# V1_PWM-to-analog_sch.net
KiCad netlist of a schematic drawn in Altium Designer
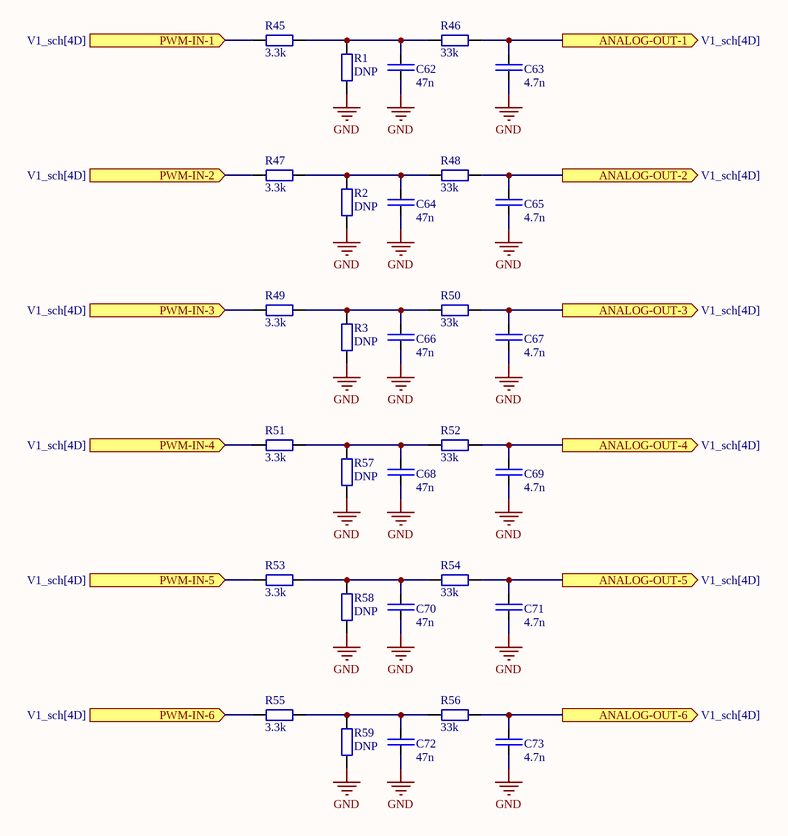
[diagram p0: V1_PWM-to-analog_sch.SchDoc]

(export (version "E")
  (design (tool "Eeschema 10.0.6"))
  (components
    (comp (ref "C62")
      (value "47n")
      (footprint "Passives:FPR_0603_C_R0")
      (description "Capacitor - generic SMD")
      (fields (field (name "Comment") "PN_C0603_TBD"))
      (libsource (lib "Passives") (part "C"))
    )
    (comp (ref "C63")
      (value "4.7n")
      (footprint "Passives:FPR_0603_C_R0")
      (description "Capacitor - generic SMD")
      (fields (field (name "Comment") "PN_C0603_TBD"))
      (libsource (lib "Passives") (part "C"))
    )
    (comp (ref "C64")
      (value "47n")
      (footprint "Passives:FPR_0603_C_R0")
      (description "Capacitor - generic SMD")
      (fields (field (name "Comment") "PN_C0603_TBD"))
      (libsource (lib "Passives") (part "C"))
    )
    (comp (ref "C65")
      (value "4.7n")
      (footprint "Passives:FPR_0603_C_R0")
      (description "Capacitor - generic SMD")
      (fields (field (name "Comment") "PN_C0603_TBD"))
      (libsource (lib "Passives") (part "C"))
    )
    (comp (ref "C66")
      (value "47n")
      (footprint "Passives:FPR_0603_C_R0")
      (description "Capacitor - generic SMD")
      (fields (field (name "Comment") "PN_C0603_TBD"))
      (libsource (lib "Passives") (part "C"))
    )
    (comp (ref "C67")
      (value "4.7n")
      (footprint "Passives:FPR_0603_C_R0")
      (description "Capacitor - generic SMD")
      (fields (field (name "Comment") "PN_C0603_TBD"))
      (libsource (lib "Passives") (part "C"))
    )
    (comp (ref "C68")
      (value "47n")
      (footprint "Passives:FPR_0603_C_R0")
      (description "Capacitor - generic SMD")
      (fields (field (name "Comment") "PN_C0603_TBD"))
      (libsource (lib "Passives") (part "C"))
    )
    (comp (ref "C69")
      (value "4.7n")
      (footprint "Passives:FPR_0603_C_R0")
      (description "Capacitor - generic SMD")
      (fields (field (name "Comment") "PN_C0603_TBD"))
      (libsource (lib "Passives") (part "C"))
    )
    (comp (ref "C70")
      (value "47n")
      (footprint "Passives:FPR_0603_C_R0")
      (description "Capacitor - generic SMD")
      (fields (field (name "Comment") "PN_C0603_TBD"))
      (libsource (lib "Passives") (part "C"))
    )
    (comp (ref "C71")
      (value "4.7n")
      (footprint "Passives:FPR_0603_C_R0")
      (description "Capacitor - generic SMD")
      (fields (field (name "Comment") "PN_C0603_TBD"))
      (libsource (lib "Passives") (part "C"))
    )
    (comp (ref "C72")
      (value "47n")
      (footprint "Passives:FPR_0603_C_R0")
      (description "Capacitor - generic SMD")
      (fields (field (name "Comment") "PN_C0603_TBD"))
      (libsource (lib "Passives") (part "C"))
    )
    (comp (ref "C73")
      (value "4.7n")
      (footprint "Passives:FPR_0603_C_R0")
      (description "Capacitor - generic SMD")
      (fields (field (name "Comment") "PN_C0603_TBD"))
      (libsource (lib "Passives") (part "C"))
    )
    (comp (ref "R1")
      (value "DNP")
      (footprint "Passives:FPR_0603_R_R0")
      (description "Resistor - generic SMD")
      (fields (field (name "Comment") "PN_R0603_TBD"))
      (libsource (lib "Passives") (part "R"))
    )
    (comp (ref "R2")
      (value "DNP")
      (footprint "Passives:FPR_0603_R_R0")
      (description "Resistor - generic SMD")
      (fields (field (name "Comment") "PN_R0603_TBD"))
      (libsource (lib "Passives") (part "R"))
    )
    (comp (ref "R3")
      (value "DNP")
      (footprint "Passives:FPR_0603_R_R0")
      (description "Resistor - generic SMD")
      (fields (field (name "Comment") "PN_R0603_TBD"))
      (libsource (lib "Passives") (part "R"))
    )
    (comp (ref "R45")
      (value "3.3k")
      (footprint "Passives:FPR_0603_R_R0")
      (description "Resistor - generic SMD")
      (fields (field (name "Comment") "PN_R0603_TBD"))
      (libsource (lib "Passives") (part "R"))
    )
    (comp (ref "R46")
      (value "33k")
      (footprint "Passives:FPR_0603_R_R0")
      (description "Resistor - generic SMD")
      (fields (field (name "Comment") "PN_R0603_TBD"))
      (libsource (lib "Passives") (part "R"))
    )
    (comp (ref "R47")
      (value "3.3k")
      (footprint "Passives:FPR_0603_R_R0")
      (description "Resistor - generic SMD")
      (fields (field (name "Comment") "PN_R0603_TBD"))
      (libsource (lib "Passives") (part "R"))
    )
    (comp (ref "R48")
      (value "33k")
      (footprint "Passives:FPR_0603_R_R0")
      (description "Resistor - generic SMD")
      (fields (field (name "Comment") "PN_R0603_TBD"))
      (libsource (lib "Passives") (part "R"))
    )
    (comp (ref "R49")
      (value "3.3k")
      (footprint "Passives:FPR_0603_R_R0")
      (description "Resistor - generic SMD")
      (fields (field (name "Comment") "PN_R0603_TBD"))
      (libsource (lib "Passives") (part "R"))
    )
    (comp (ref "R50")
      (value "33k")
      (footprint "Passives:FPR_0603_R_R0")
      (description "Resistor - generic SMD")
      (fields (field (name "Comment") "PN_R0603_TBD"))
      (libsource (lib "Passives") (part "R"))
    )
    (comp (ref "R51")
      (value "3.3k")
      (footprint "Passives:FPR_0603_R_R0")
      (description "Resistor - generic SMD")
      (fields (field (name "Comment") "PN_R0603_TBD"))
      (libsource (lib "Passives") (part "R"))
    )
    (comp (ref "R52")
      (value "33k")
      (footprint "Passives:FPR_0603_R_R0")
      (description "Resistor - generic SMD")
      (fields (field (name "Comment") "PN_R0603_TBD"))
      (libsource (lib "Passives") (part "R"))
    )
    (comp (ref "R53")
      (value "3.3k")
      (footprint "Passives:FPR_0603_R_R0")
      (description "Resistor - generic SMD")
      (fields (field (name "Comment") "PN_R0603_TBD"))
      (libsource (lib "Passives") (part "R"))
    )
    (comp (ref "R54")
      (value "33k")
      (footprint "Passives:FPR_0603_R_R0")
      (description "Resistor - generic SMD")
      (fields (field (name "Comment") "PN_R0603_TBD"))
      (libsource (lib "Passives") (part "R"))
    )
    (comp (ref "R55")
      (value "3.3k")
      (footprint "Passives:FPR_0603_R_R0")
      (description "Resistor - generic SMD")
      (fields (field (name "Comment") "PN_R0603_TBD"))
      (libsource (lib "Passives") (part "R"))
    )
    (comp (ref "R56")
      (value "33k")
      (footprint "Passives:FPR_0603_R_R0")
      (description "Resistor - generic SMD")
      (fields (field (name "Comment") "PN_R0603_TBD"))
      (libsource (lib "Passives") (part "R"))
    )
    (comp (ref "R57")
      (value "DNP")
      (footprint "Passives:FPR_0603_R_R0")
      (description "Resistor - generic SMD")
      (fields (field (name "Comment") "PN_R0603_TBD"))
      (libsource (lib "Passives") (part "R"))
    )
    (comp (ref "R58")
      (value "DNP")
      (footprint "Passives:FPR_0603_R_R0")
      (description "Resistor - generic SMD")
      (fields (field (name "Comment") "PN_R0603_TBD"))
      (libsource (lib "Passives") (part "R"))
    )
    (comp (ref "R59")
      (value "DNP")
      (footprint "Passives:FPR_0603_R_R0")
      (description "Resistor - generic SMD")
      (fields (field (name "Comment") "PN_R0603_TBD"))
      (libsource (lib "Passives") (part "R"))
    )
  )
  (nets
    (net (code "1") (name "/ANALOG-OUT-1") (class "Default")
      (node (ref "C63") (pin "2") (pinfunction "2_2") (pintype "passive"))
      (node (ref "R46") (pin "1") (pinfunction "1_1") (pintype "passive"))
    )
    (net (code "2") (name "/ANALOG-OUT-2") (class "Default")
      (node (ref "C65") (pin "2") (pinfunction "2_2") (pintype "passive"))
      (node (ref "R48") (pin "1") (pinfunction "1_1") (pintype "passive"))
    )
    (net (code "3") (name "/ANALOG-OUT-3") (class "Default")
      (node (ref "C67") (pin "2") (pinfunction "2_2") (pintype "passive"))
      (node (ref "R50") (pin "1") (pinfunction "1_1") (pintype "passive"))
    )
    (net (code "4") (name "/ANALOG-OUT-4") (class "Default")
      (node (ref "C69") (pin "2") (pinfunction "2_2") (pintype "passive"))
      (node (ref "R52") (pin "1") (pinfunction "1_1") (pintype "passive"))
    )
    (net (code "5") (name "/ANALOG-OUT-5") (class "Default")
      (node (ref "C71") (pin "2") (pinfunction "2_2") (pintype "passive"))
      (node (ref "R54") (pin "1") (pinfunction "1_1") (pintype "passive"))
    )
    (net (code "6") (name "/ANALOG-OUT-6") (class "Default")
      (node (ref "C73") (pin "2") (pinfunction "2_2") (pintype "passive"))
      (node (ref "R56") (pin "1") (pinfunction "1_1") (pintype "passive"))
    )
    (net (code "7") (name "/PWM-IN-1") (class "Default")
      (node (ref "R45") (pin "2") (pinfunction "2_2") (pintype "passive"))
    )
    (net (code "8") (name "/PWM-IN-2") (class "Default")
      (node (ref "R47") (pin "2") (pinfunction "2_2") (pintype "passive"))
    )
    (net (code "9") (name "/PWM-IN-3") (class "Default")
      (node (ref "R49") (pin "2") (pinfunction "2_2") (pintype "passive"))
    )
    (net (code "10") (name "/PWM-IN-4") (class "Default")
      (node (ref "R51") (pin "2") (pinfunction "2_2") (pintype "passive"))
    )
    (net (code "11") (name "/PWM-IN-5") (class "Default")
      (node (ref "R53") (pin "2") (pinfunction "2_2") (pintype "passive"))
    )
    (net (code "12") (name "/PWM-IN-6") (class "Default")
      (node (ref "R55") (pin "2") (pinfunction "2_2") (pintype "passive"))
    )
    (net (code "13") (name "GND") (class "Default")
      (node (ref "C62") (pin "1") (pinfunction "1_1") (pintype "passive"))
      (node (ref "C63") (pin "1") (pinfunction "1_1") (pintype "passive"))
      (node (ref "C64") (pin "1") (pinfunction "1_1") (pintype "passive"))
      (node (ref "C65") (pin "1") (pinfunction "1_1") (pintype "passive"))
      (node (ref "C66") (pin "1") (pinfunction "1_1") (pintype "passive"))
      (node (ref "C67") (pin "1") (pinfunction "1_1") (pintype "passive"))
      (node (ref "C68") (pin "1") (pinfunction "1_1") (pintype "passive"))
      (node (ref "C69") (pin "1") (pinfunction "1_1") (pintype "passive"))
      (node (ref "C70") (pin "1") (pinfunction "1_1") (pintype "passive"))
      (node (ref "C71") (pin "1") (pinfunction "1_1") (pintype "passive"))
      (node (ref "C72") (pin "1") (pinfunction "1_1") (pintype "passive"))
      (node (ref "C73") (pin "1") (pinfunction "1_1") (pintype "passive"))
      (node (ref "R1") (pin "2") (pinfunction "2_2") (pintype "passive"))
      (node (ref "R2") (pin "2") (pinfunction "2_2") (pintype "passive"))
      (node (ref "R3") (pin "2") (pinfunction "2_2") (pintype "passive"))
      (node (ref "R57") (pin "2") (pinfunction "2_2") (pintype "passive"))
      (node (ref "R58") (pin "2") (pinfunction "2_2") (pintype "passive"))
      (node (ref "R59") (pin "2") (pinfunction "2_2") (pintype "passive"))
    )
    (net (code "14") (name "Net-(C62-Pad2)") (class "Default")
      (node (ref "C62") (pin "2") (pinfunction "2_2") (pintype "passive"))
      (node (ref "R1") (pin "1") (pinfunction "1_1") (pintype "passive"))
      (node (ref "R45") (pin "1") (pinfunction "1_1") (pintype "passive"))
      (node (ref "R46") (pin "2") (pinfunction "2_2") (pintype "passive"))
    )
    (net (code "15") (name "Net-(C64-Pad2)") (class "Default")
      (node (ref "C64") (pin "2") (pinfunction "2_2") (pintype "passive"))
      (node (ref "R2") (pin "1") (pinfunction "1_1") (pintype "passive"))
      (node (ref "R47") (pin "1") (pinfunction "1_1") (pintype "passive"))
      (node (ref "R48") (pin "2") (pinfunction "2_2") (pintype "passive"))
    )
    (net (code "16") (name "Net-(C66-Pad2)") (class "Default")
      (node (ref "C66") (pin "2") (pinfunction "2_2") (pintype "passive"))
      (node (ref "R3") (pin "1") (pinfunction "1_1") (pintype "passive"))
      (node (ref "R49") (pin "1") (pinfunction "1_1") (pintype "passive"))
      (node (ref "R50") (pin "2") (pinfunction "2_2") (pintype "passive"))
    )
    (net (code "17") (name "Net-(C68-Pad2)") (class "Default")
      (node (ref "C68") (pin "2") (pinfunction "2_2") (pintype "passive"))
      (node (ref "R51") (pin "1") (pinfunction "1_1") (pintype "passive"))
      (node (ref "R52") (pin "2") (pinfunction "2_2") (pintype "passive"))
      (node (ref "R57") (pin "1") (pinfunction "1_1") (pintype "passive"))
    )
    (net (code "18") (name "Net-(C70-Pad2)") (class "Default")
      (node (ref "C70") (pin "2") (pinfunction "2_2") (pintype "passive"))
      (node (ref "R53") (pin "1") (pinfunction "1_1") (pintype "passive"))
      (node (ref "R54") (pin "2") (pinfunction "2_2") (pintype "passive"))
      (node (ref "R58") (pin "1") (pinfunction "1_1") (pintype "passive"))
    )
    (net (code "19") (name "Net-(C72-Pad2)") (class "Default")
      (node (ref "C72") (pin "2") (pinfunction "2_2") (pintype "passive"))
      (node (ref "R55") (pin "1") (pinfunction "1_1") (pintype "passive"))
      (node (ref "R56") (pin "2") (pinfunction "2_2") (pintype "passive"))
      (node (ref "R59") (pin "1") (pinfunction "1_1") (pintype "passive"))
    )
  )
)
